# power.net
KiCad netlist of a schematic drawn in Altium Designer
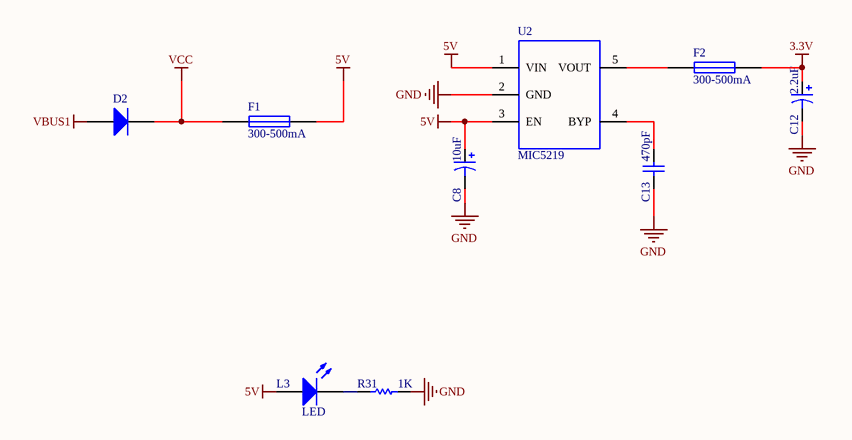
[diagram p0: power.SchDoc]

(export (version "E")
  (design (tool "Eeschema 10.0.6"))
  (components
    (comp (ref "C8")
      (value "10uF")
      (footprint "1206(2)")
      (description "Polarized Capacitor (Radial)")
      (fields (field (name "Comment") "Cap Pol1") (field (name "PUBLISHER") "Altium Limited"))
      (libsource (lib "Miscellaneous Devices") (part "Cap Pol1"))
    )
    (comp (ref "C12")
      (value "2.2uF")
      (footprint "1206(2)")
      (description "Polarized Capacitor (Radial)")
      (fields (field (name "Comment") "Cap Pol1") (field (name "PUBLISHER") "Altium Limited"))
      (libsource (lib "Miscellaneous Devices") (part "Cap Pol1"))
    )
    (comp (ref "C13")
      (value "470pF")
      (footprint "1608[0603]")
      (description "贴片电容")
      (fields (field (name "Comment") "Cap") (field (name "PUBLISHER") "Altium Limited"))
      (libsource (lib "Sparks") (part "Cap"))
    )
    (comp (ref "D2")
      (value "sk4")
      (footprint "1206(2)")
      (description "1 Amp General Purpose Rectifier")
      (fields (field (name "PUBLISHER") "Altium Limited"))
      (libsource (lib "Miscellaneous Devices") (part "Diode 1N4001"))
    )
    (comp (ref "F1")
      (value "300-500mA")
      (footprint "1206(2)")
      (description "Fuse")
      (fields (field (name "PUBLISHER") "Altium Limited"))
      (libsource (lib "K60-V4.0") (part "Fuse 1"))
    )
    (comp (ref "F2")
      (value "300-500mA")
      (footprint "1206(2)")
      (description "Fuse")
      (fields (field (name "PUBLISHER") "Altium Limited"))
      (libsource (lib "K60-V4.0") (part "Fuse 1"))
    )
    (comp (ref "L3") (value "LED") (footprint "1608[0603]") (libsource (lib "Sparks") (part "LED")))
    (comp (ref "R31")
      (value "1K")
      (footprint "1608[0603]")
      (description "贴片电阻")
      (fields (field (name "Comment") "Res") (field (name "PUBLISHER") "Altium Limited"))
      (libsource (lib "Sparks") (part "Res"))
    )
    (comp (ref "U2")
      (value "MIC5219")
      (footprint "SOT-23-5")
      (description "LDO")
      (libsource (lib "K60-V4.0") (part "MIC5219"))
    )
  )
  (nets
    (net (code "1") (name "3.3V") (class "Default")
      (node (ref "C12") (pin "1") (pinfunction "1_1") (pintype "passive"))
      (node (ref "F2") (pin "2") (pinfunction "2_2") (pintype "passive"))
    )
    (net (code "2") (name "5V") (class "Default")
      (node (ref "C8") (pin "1") (pinfunction "1_1") (pintype "passive"))
      (node (ref "F1") (pin "2") (pinfunction "2_2") (pintype "passive"))
      (node (ref "L3") (pin "1") (pinfunction "A_1") (pintype "passive"))
      (node (ref "U2") (pin "1") (pinfunction "VIN_1") (pintype "passive"))
      (node (ref "U2") (pin "3") (pinfunction "EN_3") (pintype "passive"))
    )
    (net (code "3") (name "GND") (class "Default")
      (node (ref "C12") (pin "2") (pinfunction "2_2") (pintype "passive"))
      (node (ref "C13") (pin "1") (pinfunction "1_1") (pintype "passive"))
      (node (ref "C8") (pin "2") (pinfunction "2_2") (pintype "passive"))
      (node (ref "R31") (pin "1") (pinfunction "1_1") (pintype "passive"))
      (node (ref "U2") (pin "2") (pinfunction "GND_2") (pintype "passive"))
    )
    (net (code "4") (name "Net-(L3-K)") (class "Default")
      (node (ref "L3") (pin "2") (pinfunction "K_2") (pintype "passive"))
      (node (ref "R31") (pin "2") (pinfunction "2_2") (pintype "passive"))
    )
    (net (code "5") (name "Net-(U2-BYP)") (class "Default")
      (node (ref "C13") (pin "2") (pinfunction "2_2") (pintype "passive"))
      (node (ref "U2") (pin "4") (pinfunction "BYP_4") (pintype "passive"))
    )
    (net (code "6") (name "Net-(U2-VOUT)") (class "Default")
      (node (ref "F2") (pin "1") (pinfunction "1_1") (pintype "passive"))
      (node (ref "U2") (pin "5") (pinfunction "VOUT_5") (pintype "passive"))
    )
    (net (code "7") (name "VBUS1") (class "Default")
      (node (ref "D2") (pin "1") (pinfunction "A_1") (pintype "passive"))
    )
    (net (code "8") (name "VCC") (class "Default")
      (node (ref "D2") (pin "2") (pinfunction "K_2") (pintype "passive"))
      (node (ref "F1") (pin "1") (pinfunction "1_1") (pintype "passive"))
    )
  )
)
